# 280112_Battery_Connector_UEBK-30257_1_1.net
KiCad netlist of a schematic drawn in EAGLE
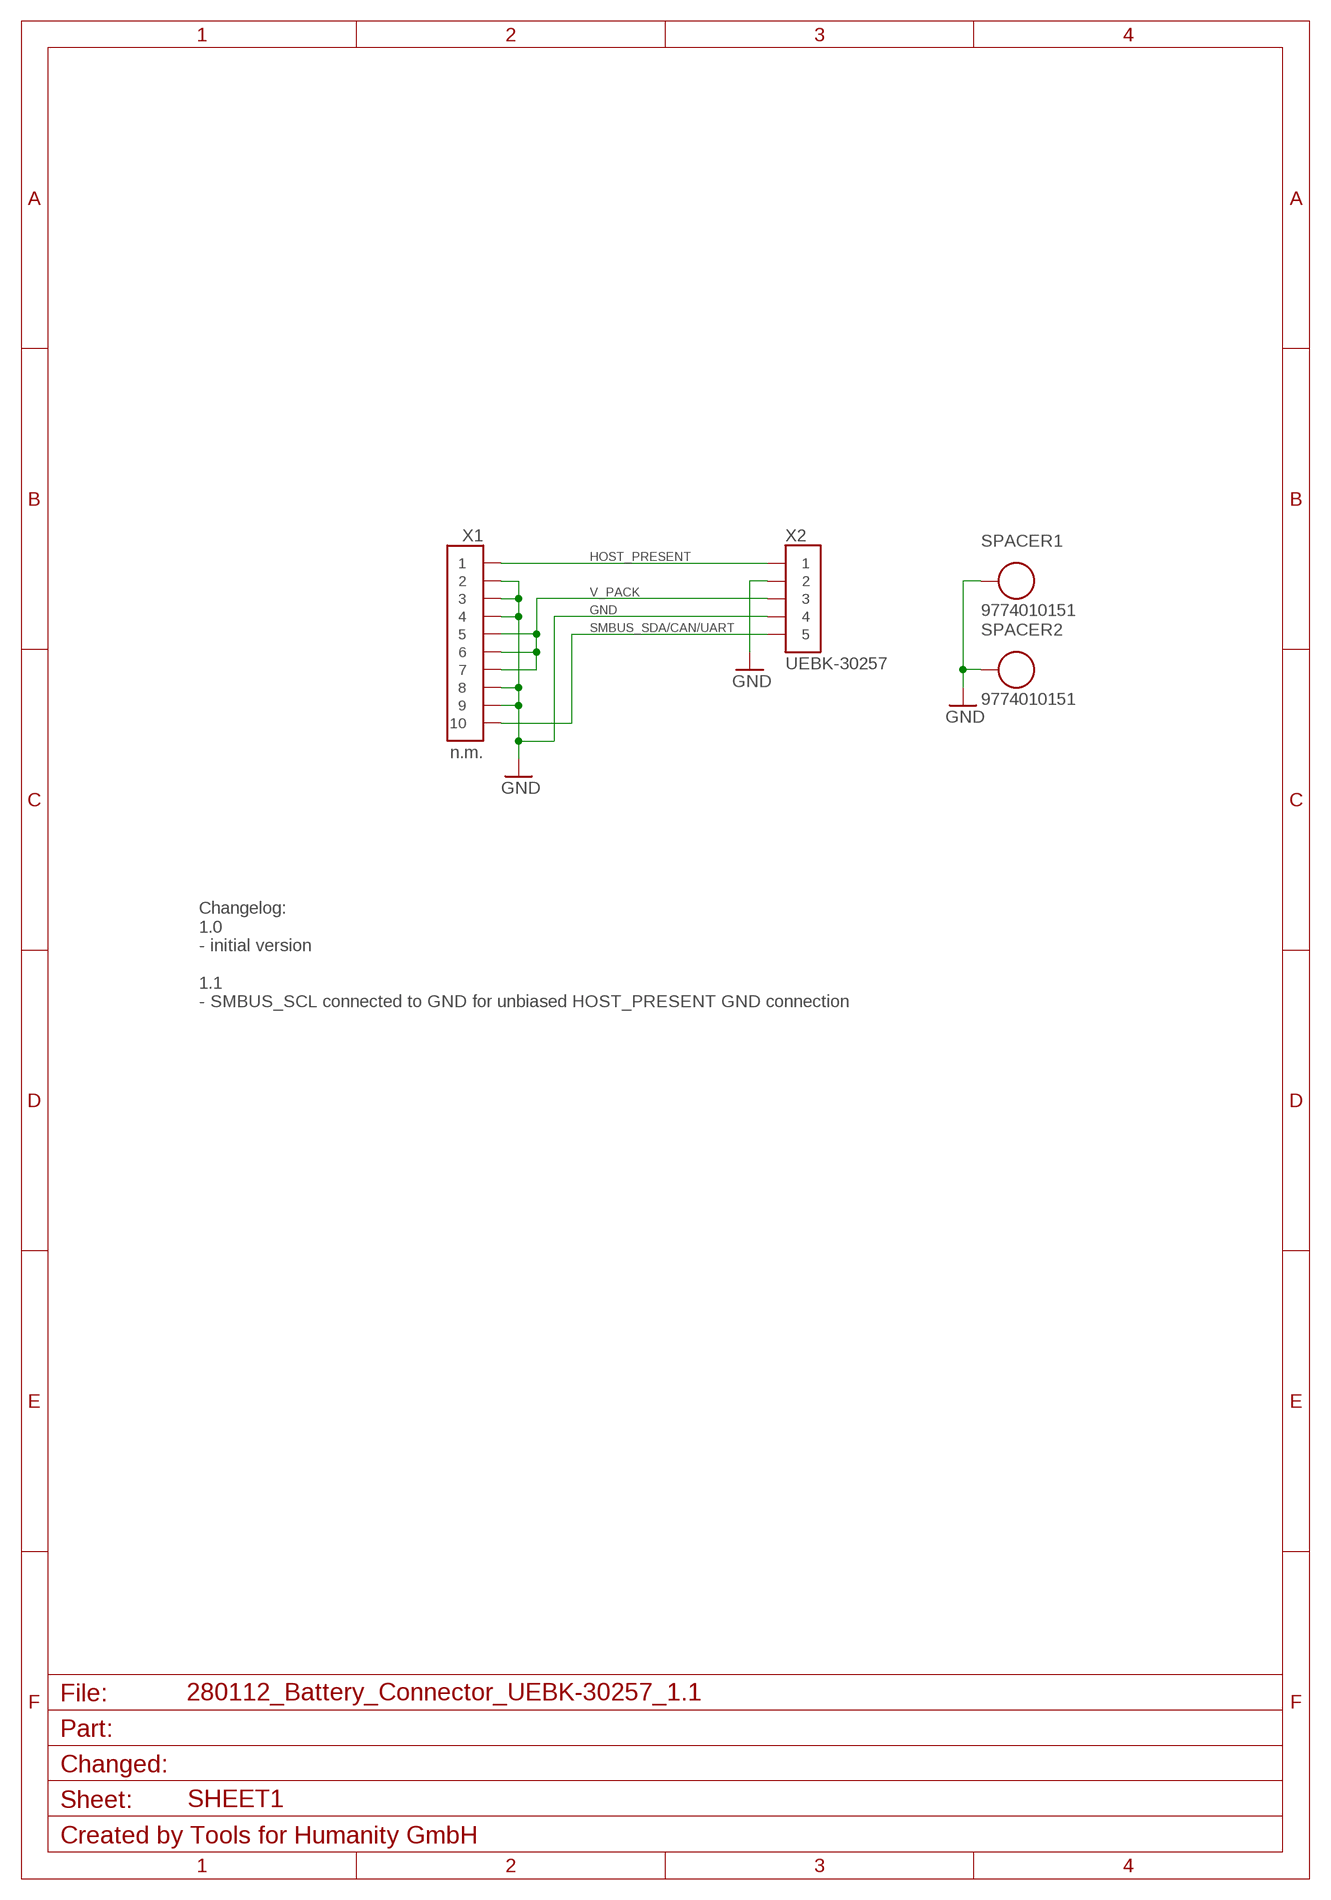
[diagram p0: schematic, sheet 1]

(export (version "E")
  (design (tool "Eeschema 10.0.6"))
  (components
    (comp (ref "SPACER1")
      (value "9774010151")
      (footprint "eagle-import:WA-SMSI_9774010151_WUERTH")
      (fields (field (name "MANUFACTURER") "Wuerth"))
      (libsource (lib "eagle-import") (part "9774010151"))
    )
    (comp (ref "SPACER2")
      (value "9774010151")
      (footprint "eagle-import:WA-SMSI_9774010151_WUERTH")
      (fields (field (name "MANUFACTURER") "Wuerth"))
      (libsource (lib "eagle-import") (part "9774010151"))
    )
    (comp (ref "X1")
      (value "n.m.")
      (footprint "eagle-import:61301011121_WUERTH")
      (fields (field (name "MANUFACTURER") "Wuerth") (field (name "VOLTAGE") "500 V(AC)"))
      (libsource (lib "eagle-import") (part "61301011121"))
    )
    (comp (ref "X2")
      (value "UEBK-30257")
      (footprint "eagle-import:UEBK-30257_UWE")
      (fields (field (name "MANUFACTURER") "uwe electronic GmbH"))
      (libsource (lib "eagle-import") (part "UEBK-30257"))
    )
  )
  (nets
    (net (code "1") (name "/HOST_PRESENT") (class "Default")
      (node (ref "X1") (pin "1") (pinfunction "1_1") (pintype "passive"))
      (node (ref "X2") (pin "1") (pinfunction "1_1") (pintype "passive"))
    )
    (net (code "2") (name "/SMBUS_SDA{slash}CAN{slash}UART") (class "Default")
      (node (ref "X1") (pin "10") (pinfunction "10_10") (pintype "passive"))
      (node (ref "X2") (pin "5") (pinfunction "5_5") (pintype "passive"))
    )
    (net (code "3") (name "/V_PACK") (class "Default")
      (node (ref "X1") (pin "5") (pinfunction "5_5") (pintype "passive"))
      (node (ref "X1") (pin "6") (pinfunction "6_6") (pintype "passive"))
      (node (ref "X1") (pin "7") (pinfunction "7_7") (pintype "passive"))
      (node (ref "X2") (pin "3") (pinfunction "3_3") (pintype "passive"))
    )
    (net (code "4") (name "GND") (class "Default")
      (node (ref "SPACER1") (pin "2") (pinfunction "1_2") (pintype "passive"))
      (node (ref "SPACER1") (pin "3") (pinfunction "1_3") (pintype "passive"))
      (node (ref "SPACER2") (pin "2") (pinfunction "1_2") (pintype "passive"))
      (node (ref "SPACER2") (pin "3") (pinfunction "1_3") (pintype "passive"))
      (node (ref "X1") (pin "2") (pinfunction "2_2") (pintype "passive"))
      (node (ref "X1") (pin "3") (pinfunction "3_3") (pintype "passive"))
      (node (ref "X1") (pin "4") (pinfunction "4_4") (pintype "passive"))
      (node (ref "X1") (pin "8") (pinfunction "8_8") (pintype "passive"))
      (node (ref "X1") (pin "9") (pinfunction "9_9") (pintype "passive"))
      (node (ref "X2") (pin "2") (pinfunction "2_2") (pintype "passive"))
      (node (ref "X2") (pin "4") (pinfunction "4_4") (pintype "passive"))
    )
  )
)
